# drive-adaptor.net
KiCad netlist of a schematic drawn in EAGLE
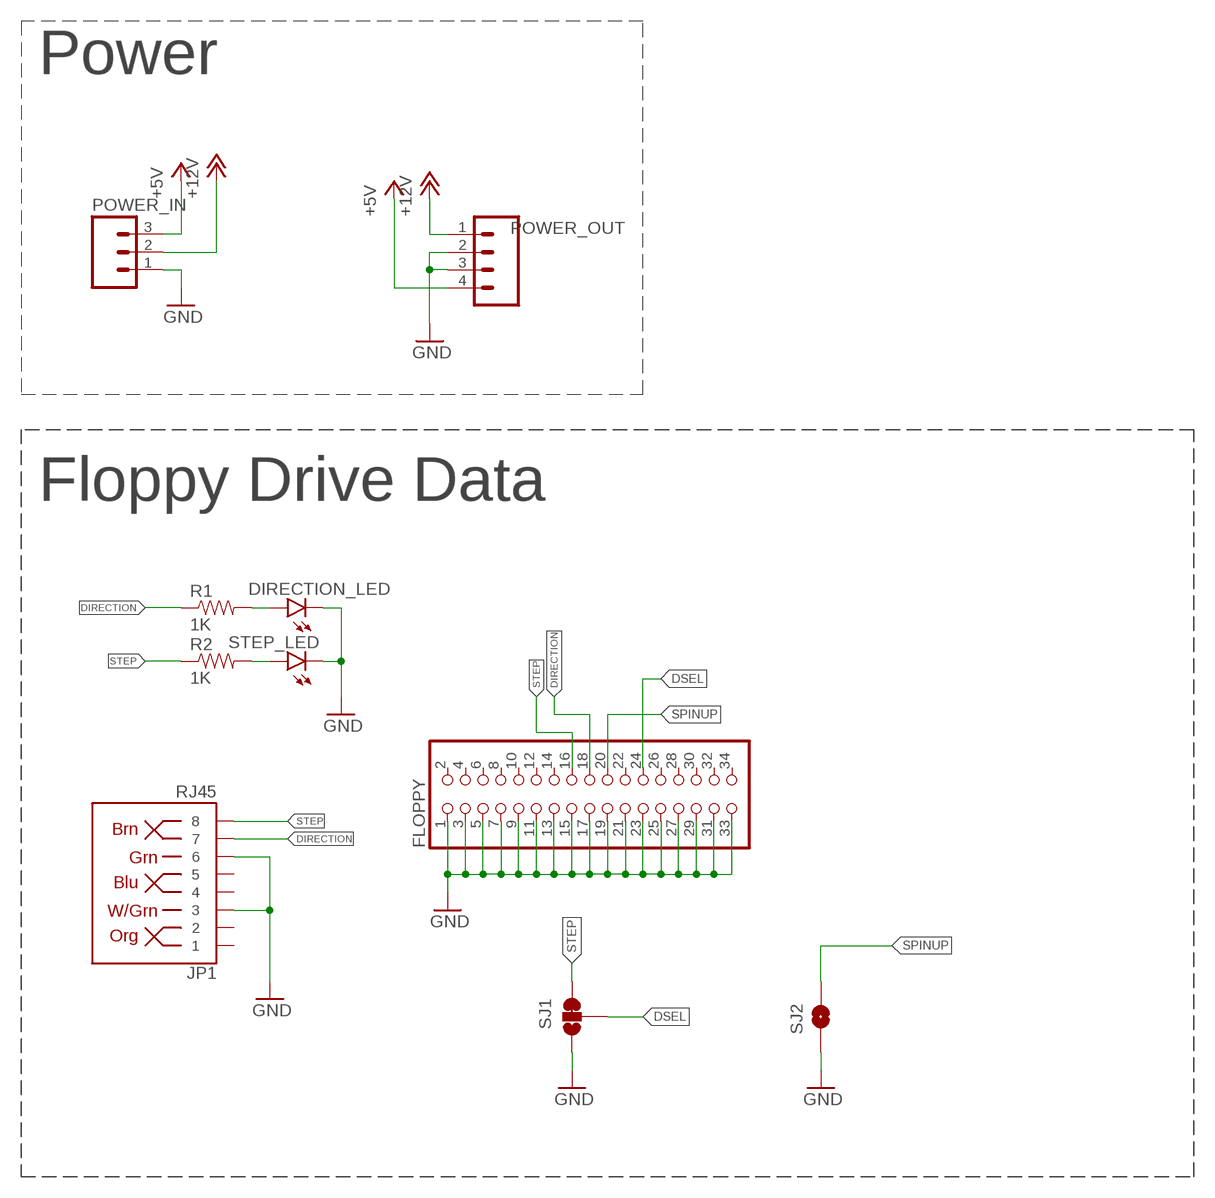
[diagram p0: schematic, sheet 1]

(export (version "E")
  (design (tool "Eeschema 10.0.6"))
  (components
    (comp (ref "DIRECTION_LED")
      (value "LED1206")
      (footprint "eagle-import:LED-1206")
      (libsource (lib "eagle-import") (part "LED1206"))
    )
    (comp (ref "FLOPPY")
      (value "PINHD-2X17")
      (footprint "eagle-import:2X17")
      (libsource (lib "eagle-import") (part "PINHD-2X17"))
    )
    (comp (ref "JP1")
      (value "RJ45")
      (footprint "eagle-import:RJ45-8")
      (libsource (lib "eagle-import") (part "RJ45-8PTH"))
    )
    (comp (ref "POWER_IN")
      (value "M03-SCREW-5MM")
      (footprint "eagle-import:SCREWTERMINAL-5MM-3")
      (libsource (lib "eagle-import") (part "M03-SCREW-5MM"))
    )
    (comp (ref "POWER_OUT")
      (value "M04LONGPADS")
      (footprint "eagle-import:1X04_LONGPADS")
      (libsource (lib "eagle-import") (part "M04LONGPADS"))
    )
    (comp (ref "R1")
      (value "1K")
      (footprint "eagle-import:0603-RES")
      (libsource (lib "eagle-import") (part "1KOHM-1/10W-1%(0603)"))
    )
    (comp (ref "R2")
      (value "1K")
      (footprint "eagle-import:0603-RES")
      (libsource (lib "eagle-import") (part "1KOHM-1/10W-1%(0603)"))
    )
    (comp (ref "SJ1")
      (value "JUMPER-PAD-3-2OF3_NC_BY_TRACE_SMALL")
      (footprint "eagle-import:PAD-JUMPER-3-2OF3_NC_BY_TRACE_YES_SILK_FULL_BOX")
      (libsource (lib "eagle-import") (part "JUMPER-PAD-3-2OF3_NC_BY_TRACE_SMALL"))
    )
    (comp (ref "SJ2")
      (value "JUMPER-PAD-2-NOYES_SILK")
      (footprint "eagle-import:PAD-JUMPER-2-NO_YES_SILK")
      (libsource (lib "eagle-import") (part "JUMPER-PAD-2-NOYES_SILK"))
    )
    (comp (ref "STEP_LED")
      (value "LED1206")
      (footprint "eagle-import:LED-1206")
      (libsource (lib "eagle-import") (part "LED1206"))
    )
  )
  (nets
    (net (code "1") (name "+5V") (class "Default")
      (node (ref "POWER_IN") (pin "3") (pinfunction "3_3") (pintype "passive"))
      (node (ref "POWER_OUT") (pin "4") (pinfunction "4_4") (pintype "passive"))
    )
    (net (code "2") (name "+12V") (class "Default")
      (node (ref "POWER_IN") (pin "2") (pinfunction "2_2") (pintype "passive"))
      (node (ref "POWER_OUT") (pin "1") (pinfunction "1_1") (pintype "passive"))
    )
    (net (code "3") (name "DIRECTION") (class "Default")
      (node (ref "FLOPPY") (pin "18") (pinfunction "18_18") (pintype "passive"))
      (node (ref "JP1") (pin "7") (pinfunction "7_7") (pintype "bidirectional"))
      (node (ref "R1") (pin "1") (pinfunction "1_1") (pintype "passive"))
    )
    (net (code "4") (name "DSEL") (class "Default")
      (node (ref "FLOPPY") (pin "24") (pinfunction "24_24") (pintype "passive"))
      (node (ref "SJ1") (pin "2") (pinfunction "2_2") (pintype "passive"))
    )
    (net (code "5") (name "GND") (class "Default")
      (node (ref "DIRECTION_LED") (pin "C") (pinfunction "C_C") (pintype "passive"))
      (node (ref "FLOPPY") (pin "1") (pinfunction "1_1") (pintype "passive"))
      (node (ref "FLOPPY") (pin "11") (pinfunction "11_11") (pintype "passive"))
      (node (ref "FLOPPY") (pin "13") (pinfunction "13_13") (pintype "passive"))
      (node (ref "FLOPPY") (pin "15") (pinfunction "15_15") (pintype "passive"))
      (node (ref "FLOPPY") (pin "17") (pinfunction "17_17") (pintype "passive"))
      (node (ref "FLOPPY") (pin "19") (pinfunction "19_19") (pintype "passive"))
      (node (ref "FLOPPY") (pin "21") (pinfunction "21_21") (pintype "passive"))
      (node (ref "FLOPPY") (pin "23") (pinfunction "23_23") (pintype "passive"))
      (node (ref "FLOPPY") (pin "25") (pinfunction "25_25") (pintype "passive"))
      (node (ref "FLOPPY") (pin "27") (pinfunction "27_27") (pintype "passive"))
      (node (ref "FLOPPY") (pin "29") (pinfunction "29_29") (pintype "passive"))
      (node (ref "FLOPPY") (pin "3") (pinfunction "3_3") (pintype "passive"))
      (node (ref "FLOPPY") (pin "31") (pinfunction "31_31") (pintype "passive"))
      (node (ref "FLOPPY") (pin "33") (pinfunction "33_33") (pintype "passive"))
      (node (ref "FLOPPY") (pin "5") (pinfunction "5_5") (pintype "passive"))
      (node (ref "FLOPPY") (pin "7") (pinfunction "7_7") (pintype "passive"))
      (node (ref "FLOPPY") (pin "9") (pinfunction "9_9") (pintype "passive"))
      (node (ref "JP1") (pin "3") (pinfunction "3_3") (pintype "bidirectional"))
      (node (ref "JP1") (pin "6") (pinfunction "6_6") (pintype "bidirectional"))
      (node (ref "POWER_IN") (pin "1") (pinfunction "1_1") (pintype "passive"))
      (node (ref "POWER_OUT") (pin "2") (pinfunction "2_2") (pintype "passive"))
      (node (ref "POWER_OUT") (pin "3") (pinfunction "3_3") (pintype "passive"))
      (node (ref "SJ1") (pin "1") (pinfunction "1_1") (pintype "passive"))
      (node (ref "SJ2") (pin "1") (pinfunction "1_1") (pintype "passive"))
      (node (ref "STEP_LED") (pin "C") (pinfunction "C_C") (pintype "passive"))
    )
    (net (code "6") (name "Net-(DIRECTION_LED-PadA)") (class "Default")
      (node (ref "DIRECTION_LED") (pin "A") (pinfunction "A_A") (pintype "passive"))
      (node (ref "R1") (pin "2") (pinfunction "2_2") (pintype "passive"))
    )
    (net (code "7") (name "Net-(R2-Pad2)") (class "Default")
      (node (ref "R2") (pin "2") (pinfunction "2_2") (pintype "passive"))
      (node (ref "STEP_LED") (pin "A") (pinfunction "A_A") (pintype "passive"))
    )
    (net (code "8") (name "SPINUP") (class "Default")
      (node (ref "FLOPPY") (pin "20") (pinfunction "20_20") (pintype "passive"))
      (node (ref "SJ2") (pin "2") (pinfunction "2_2") (pintype "passive"))
    )
    (net (code "9") (name "STEP") (class "Default")
      (node (ref "FLOPPY") (pin "16") (pinfunction "16_16") (pintype "passive"))
      (node (ref "JP1") (pin "8") (pinfunction "8_8") (pintype "bidirectional"))
      (node (ref "R2") (pin "1") (pinfunction "1_1") (pintype "passive"))
      (node (ref "SJ1") (pin "3") (pinfunction "3_3") (pintype "passive"))
    )
    (net (code "10") (name "unconnected-(FLOPPY-Pad2)") (class "Default")
      (node (ref "FLOPPY") (pin "2") (pinfunction "2_2") (pintype "passive"))
    )
    (net (code "11") (name "unconnected-(FLOPPY-Pad4)") (class "Default")
      (node (ref "FLOPPY") (pin "4") (pinfunction "4_4") (pintype "passive"))
    )
    (net (code "12") (name "unconnected-(FLOPPY-Pad6)") (class "Default")
      (node (ref "FLOPPY") (pin "6") (pinfunction "6_6") (pintype "passive"))
    )
    (net (code "13") (name "unconnected-(FLOPPY-Pad8)") (class "Default")
      (node (ref "FLOPPY") (pin "8") (pinfunction "8_8") (pintype "passive"))
    )
    (net (code "14") (name "unconnected-(FLOPPY-Pad10)") (class "Default")
      (node (ref "FLOPPY") (pin "10") (pinfunction "10_10") (pintype "passive"))
    )
    (net (code "15") (name "unconnected-(FLOPPY-Pad12)") (class "Default")
      (node (ref "FLOPPY") (pin "12") (pinfunction "12_12") (pintype "passive"))
    )
    (net (code "16") (name "unconnected-(FLOPPY-Pad14)") (class "Default")
      (node (ref "FLOPPY") (pin "14") (pinfunction "14_14") (pintype "passive"))
    )
    (net (code "17") (name "unconnected-(FLOPPY-Pad22)") (class "Default")
      (node (ref "FLOPPY") (pin "22") (pinfunction "22_22") (pintype "passive"))
    )
    (net (code "18") (name "unconnected-(FLOPPY-Pad26)") (class "Default")
      (node (ref "FLOPPY") (pin "26") (pinfunction "26_26") (pintype "passive"))
    )
    (net (code "19") (name "unconnected-(FLOPPY-Pad28)") (class "Default")
      (node (ref "FLOPPY") (pin "28") (pinfunction "28_28") (pintype "passive"))
    )
    (net (code "20") (name "unconnected-(FLOPPY-Pad30)") (class "Default")
      (node (ref "FLOPPY") (pin "30") (pinfunction "30_30") (pintype "passive"))
    )
    (net (code "21") (name "unconnected-(FLOPPY-Pad32)") (class "Default")
      (node (ref "FLOPPY") (pin "32") (pinfunction "32_32") (pintype "passive"))
    )
    (net (code "22") (name "unconnected-(FLOPPY-Pad34)") (class "Default")
      (node (ref "FLOPPY") (pin "34") (pinfunction "34_34") (pintype "passive"))
    )
    (net (code "23") (name "unconnected-(JP1-Pad1)") (class "Default")
      (node (ref "JP1") (pin "1") (pinfunction "1_1") (pintype "bidirectional"))
    )
    (net (code "24") (name "unconnected-(JP1-Pad2)") (class "Default")
      (node (ref "JP1") (pin "2") (pinfunction "2_2") (pintype "bidirectional"))
    )
    (net (code "25") (name "unconnected-(JP1-Pad4)") (class "Default")
      (node (ref "JP1") (pin "4") (pinfunction "4_4") (pintype "bidirectional"))
    )
    (net (code "26") (name "unconnected-(JP1-Pad5)") (class "Default")
      (node (ref "JP1") (pin "5") (pinfunction "5_5") (pintype "bidirectional"))
    )
  )
)
